# Schematic.net
KiCad netlist of a schematic drawn in Altium Designer
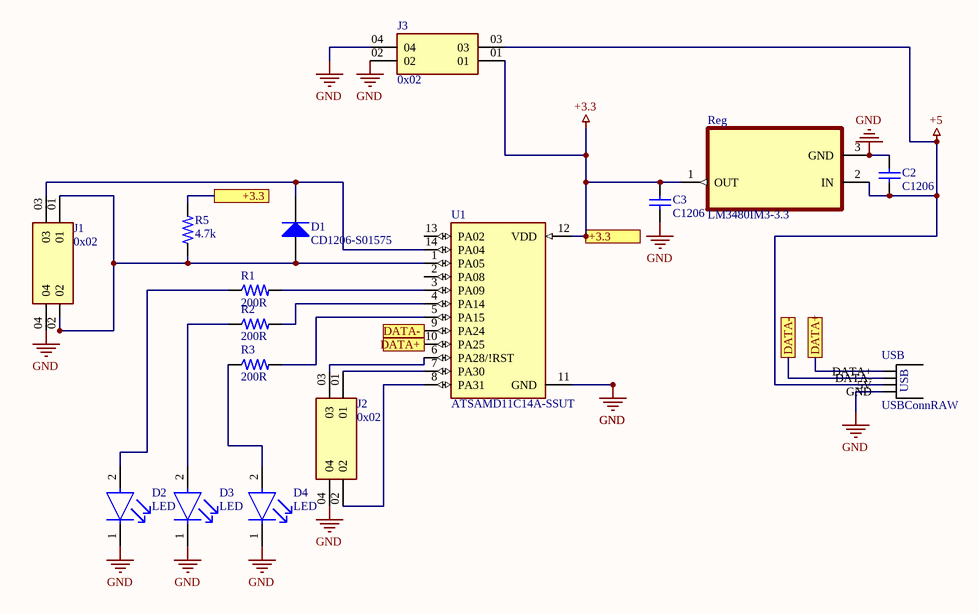
[diagram p0: Schematic.SchDoc]

(export (version "E")
  (design (tool "Eeschema 10.0.6"))
  (components
    (comp (ref "C2")
      (value "C1206")
      (footprint "KEMT-1206-2_M")
      (description "CAP, Ceramic, 0.1 uF, +/- 10%, 50 V, -55 to 125 degC, 1206 (3216 Metric), RoHS, Tape and Reel")
      (fields (field (name "MANUFACTURER") "Kemet"))
      (libsource (lib "Altium Content Vault") (part "CAP-NP-2"))
    )
    (comp (ref "C3")
      (value "C1206")
      (footprint "KEMT-1206-2_M")
      (description "CAP, Ceramic, 0.1 uF, +/- 10%, 50 V, -55 to 125 degC, 1206 (3216 Metric), RoHS, Tape and Reel")
      (fields (field (name "MANUFACTURER") "Kemet"))
      (libsource (lib "Altium Content Vault") (part "CAP-NP-2"))
    )
    (comp (ref "D1")
      (value "CD1206-S01575")
      (footprint "BOUR-CD1206-S01575-2_L")
      (description "75 V Small Signal Switching Diode, 150 mA, 2.5 uA, 1026 Molded Package, RoHS, Tape and Reel")
      (fields (field (name "MANUFACTURER") "Bourns"))
      (libsource (lib "Altium Content Vault") (part "BOUR-A1K2-2"))
    )
    (comp (ref "D2")
      (value "LED")
      (footprint "FP-APTD3216CGCK-MFG")
      (description "LED GREEN CLEAR 2SMD")
      (libsource (lib "Altium Content Vault") (part "8706943c75ba83719d021d2fdc84c58"))
    )
    (comp (ref "D3")
      (value "LED")
      (footprint "FP-APTD3216CGCK-MFG")
      (description "LED GREEN CLEAR 2SMD")
      (libsource (lib "Altium Content Vault") (part "8706943c75ba83719d021d2fdc84c58"))
    )
    (comp (ref "D4")
      (value "LED")
      (footprint "FP-APTD3216CGCK-MFG")
      (description "LED GREEN CLEAR 2SMD")
      (libsource (lib "Altium Content Vault") (part "8706943c75ba83719d021d2fdc84c58"))
    )
    (comp (ref "J1")
      (value "0x02")
      (footprint "SAMTEC_TSM-102-02-T-DV")
      (description "TSM - Samtec 2.54mm Dual Row Vertical Surface Mount Header 8.13mm Post Height (02) - Fast Stock")
      (fields (field (name "MP") "TSM-102-02-T-DV") (field (name "MF") "Samtec Inc."))
      (libsource (lib "TSM-102-02-T-DV") (part "TSM-102-02-T-DV"))
    )
    (comp (ref "J2")
      (value "0x02")
      (footprint "SAMTEC_TSM-102-02-T-DV")
      (description "TSM - Samtec 2.54mm Dual Row Vertical Surface Mount Header 8.13mm Post Height (02) - Fast Stock")
      (fields (field (name "MP") "TSM-102-02-T-DV") (field (name "MF") "Samtec Inc."))
      (libsource (lib "TSM-102-02-T-DV") (part "TSM-102-02-T-DV"))
    )
    (comp (ref "J3")
      (value "0x02")
      (footprint "SAMTEC_TSM-102-02-T-DV")
      (description "TSM - Samtec 2.54mm Dual Row Vertical Surface Mount Header 8.13mm Post Height (02) - Fast Stock")
      (fields (field (name "MP") "TSM-102-02-T-DV") (field (name "MF") "Samtec Inc."))
      (libsource (lib "") (part "TSM-102-02-T-DV_1"))
    )
    (comp (ref "R1")
      (value "200R")
      (footprint "RESC3115X65N")
      (description "CRGS1206 5% 2K7")
      (fields (field (name "MP") "4-2176245-2"))
      (libsource (lib "Res1206") (part "4-2176245-2"))
    )
    (comp (ref "R2")
      (value "200R")
      (footprint "RESC3115X65N")
      (description "CRGS1206 5% 2K7")
      (fields (field (name "MP") "4-2176245-2"))
      (libsource (lib "Res1206") (part "4-2176245-2"))
    )
    (comp (ref "R3")
      (value "200R")
      (footprint "RESC3115X65N")
      (description "CRGS1206 5% 2K7")
      (fields (field (name "MP") "4-2176245-2"))
      (libsource (lib "Res1206") (part "4-2176245-2"))
    )
    (comp (ref "R5")
      (value "4.7k")
      (footprint "RESC3115X65N")
      (description "CRGS1206 5% 2K7")
      (fields (field (name "MP") "4-2176245-2"))
      (libsource (lib "Res1206") (part "4-2176245-2"))
    )
    (comp (ref "Reg")
      (value "LM3480IM3-3.3")
      (footprint "SOT95P251X112-3N")
      (description "100-mA, 30-V, low-dropout voltage regulator 3-SOT-23 -40 to 125")
      (fields (field (name "MP") "LM3480IM3-3.3/NOPB") (field (name "MF") "Texas"))
      (libsource (lib "LM3480IM3-3.3") (part "LM3480IM3-3.3"))
    )
    (comp (ref "U1")
      (value "ATSAMD11C14A-SSUT")
      (footprint "SOIC127P600X160-14N")
      (description "MCU 32-Bit SAM D11 ARM Cortex M0+ RISC 16KB Flash 1.8V/2.5V/3.3V 14-Pin SOIC T/R")
      (libsource (lib "ATSAMD11C14A-SSUT") (part "ATSAMD11C14A-SSUT"))
    )
    (comp (ref "USB")
      (value "USBConnRAW")
      (footprint "USBConnRAW")
      (description "USB Connector directly on the PCB, without connector")
      (libsource (lib "USBConnRAW") (part "USBConnRAW"))
    )
  )
  (nets
    (net (code "1") (name "+3.3") (class "Default")
      (node (ref "C3") (pin "2") (pinfunction "2_2") (pintype "passive"))
      (node (ref "J3") (pin "01") (pinfunction "01_01") (pintype "passive"))
      (node (ref "R5") (pin "1") (pinfunction "1_1") (pintype "passive"))
      (node (ref "Reg") (pin "1") (pinfunction "OUT_1") (pintype "output"))
      (node (ref "U1") (pin "12") (pinfunction "VDD_12") (pintype "input"))
    )
    (net (code "2") (name "+5") (class "Default")
      (node (ref "C2") (pin "2") (pinfunction "2_2") (pintype "passive"))
      (node (ref "J3") (pin "03") (pinfunction "03_03") (pintype "passive"))
      (node (ref "Reg") (pin "2") (pinfunction "IN_2") (pintype "power_in"))
      (node (ref "USB") (pin "5V") (pinfunction "5V_5V") (pintype "passive"))
    )
    (net (code "3") (name "/DATA+") (class "Default")
      (node (ref "U1") (pin "10") (pinfunction "PA25_10") (pintype "bidirectional"))
      (node (ref "USB") (pin "DATA+") (pinfunction "DATA+_DATA+") (pintype "passive"))
    )
    (net (code "4") (name "/DATA-") (class "Default")
      (node (ref "U1") (pin "9") (pinfunction "PA24_9") (pintype "bidirectional"))
      (node (ref "USB") (pin "DATA-") (pinfunction "DATA-_DATA-") (pintype "passive"))
    )
    (net (code "5") (name "GND") (class "Default")
      (node (ref "C2") (pin "1") (pinfunction "1_1") (pintype "passive"))
      (node (ref "C3") (pin "1") (pinfunction "1_1") (pintype "passive"))
      (node (ref "D2") (pin "1") (pinfunction "C_1") (pintype "passive"))
      (node (ref "D3") (pin "1") (pinfunction "C_1") (pintype "passive"))
      (node (ref "D4") (pin "1") (pinfunction "C_1") (pintype "passive"))
      (node (ref "J1") (pin "04") (pinfunction "04_04") (pintype "passive"))
      (node (ref "J2") (pin "04") (pinfunction "04_04") (pintype "passive"))
      (node (ref "J3") (pin "02") (pinfunction "02_02") (pintype "passive"))
      (node (ref "J3") (pin "04") (pinfunction "04_04") (pintype "passive"))
      (node (ref "Reg") (pin "3") (pinfunction "GND_3") (pintype "passive"))
      (node (ref "U1") (pin "11") (pinfunction "GND_11") (pintype "power_in"))
      (node (ref "USB") (pin "GND") (pinfunction "GND_GND") (pintype "passive"))
    )
    (net (code "6") (name "Net-(D1-A)") (class "Default")
      (node (ref "D1") (pin "1") (pinfunction "A_1") (pintype "passive"))
      (node (ref "J1") (pin "01") (pinfunction "01_01") (pintype "passive"))
      (node (ref "J1") (pin "02") (pinfunction "02_02") (pintype "passive"))
      (node (ref "R5") (pin "2") (pinfunction "2_2") (pintype "passive"))
      (node (ref "U1") (pin "1") (pinfunction "PA05_1") (pintype "bidirectional"))
    )
    (net (code "7") (name "Net-(D1-K)") (class "Default")
      (node (ref "D1") (pin "2") (pinfunction "K_2") (pintype "passive"))
      (node (ref "J1") (pin "03") (pinfunction "03_03") (pintype "passive"))
      (node (ref "U1") (pin "14") (pinfunction "PA04_14") (pintype "bidirectional"))
    )
    (net (code "8") (name "Net-(D2-A)") (class "Default")
      (node (ref "D2") (pin "2") (pinfunction "A_2") (pintype "passive"))
      (node (ref "R1") (pin "1") (pinfunction "1_1") (pintype "passive"))
    )
    (net (code "9") (name "Net-(D3-A)") (class "Default")
      (node (ref "D3") (pin "2") (pinfunction "A_2") (pintype "passive"))
      (node (ref "R2") (pin "1") (pinfunction "1_1") (pintype "passive"))
    )
    (net (code "10") (name "Net-(D4-A)") (class "Default")
      (node (ref "D4") (pin "2") (pinfunction "A_2") (pintype "passive"))
      (node (ref "R3") (pin "1") (pinfunction "1_1") (pintype "passive"))
    )
    (net (code "11") (name "Net-(U1-PA09)") (class "Default")
      (node (ref "R1") (pin "2") (pinfunction "2_2") (pintype "passive"))
      (node (ref "U1") (pin "3") (pinfunction "PA09_3") (pintype "bidirectional"))
    )
    (net (code "12") (name "Net-(U1-PA14)") (class "Default")
      (node (ref "R2") (pin "2") (pinfunction "2_2") (pintype "passive"))
      (node (ref "U1") (pin "4") (pinfunction "PA14_4") (pintype "bidirectional"))
    )
    (net (code "13") (name "Net-(U1-PA15)") (class "Default")
      (node (ref "R3") (pin "2") (pinfunction "2_2") (pintype "passive"))
      (node (ref "U1") (pin "5") (pinfunction "PA15_5") (pintype "bidirectional"))
    )
    (net (code "14") (name "Net-(U1-PA28{slash}!RST)") (class "Default")
      (node (ref "J2") (pin "03") (pinfunction "03_03") (pintype "passive"))
      (node (ref "U1") (pin "6") (pinfunction "PA28/!RST_6") (pintype "bidirectional"))
    )
    (net (code "15") (name "Net-(U1-PA30)") (class "Default")
      (node (ref "J2") (pin "01") (pinfunction "01_01") (pintype "passive"))
      (node (ref "U1") (pin "7") (pinfunction "PA30_7") (pintype "bidirectional"))
    )
    (net (code "16") (name "Net-(U1-PA31)") (class "Default")
      (node (ref "J2") (pin "02") (pinfunction "02_02") (pintype "passive"))
      (node (ref "U1") (pin "8") (pinfunction "PA31_8") (pintype "bidirectional"))
    )
    (net (code "17") (name "unconnected-(U1-PA02-Pad13)") (class "Default")
      (node (ref "U1") (pin "13") (pinfunction "PA02_13") (pintype "bidirectional"))
    )
    (net (code "18") (name "unconnected-(U1-PA08-Pad2)") (class "Default")
      (node (ref "U1") (pin "2") (pinfunction "PA08_2") (pintype "bidirectional"))
    )
  )
)
